# 3_adcs_circuits.net
KiCad netlist of a schematic drawn in Altium Designer
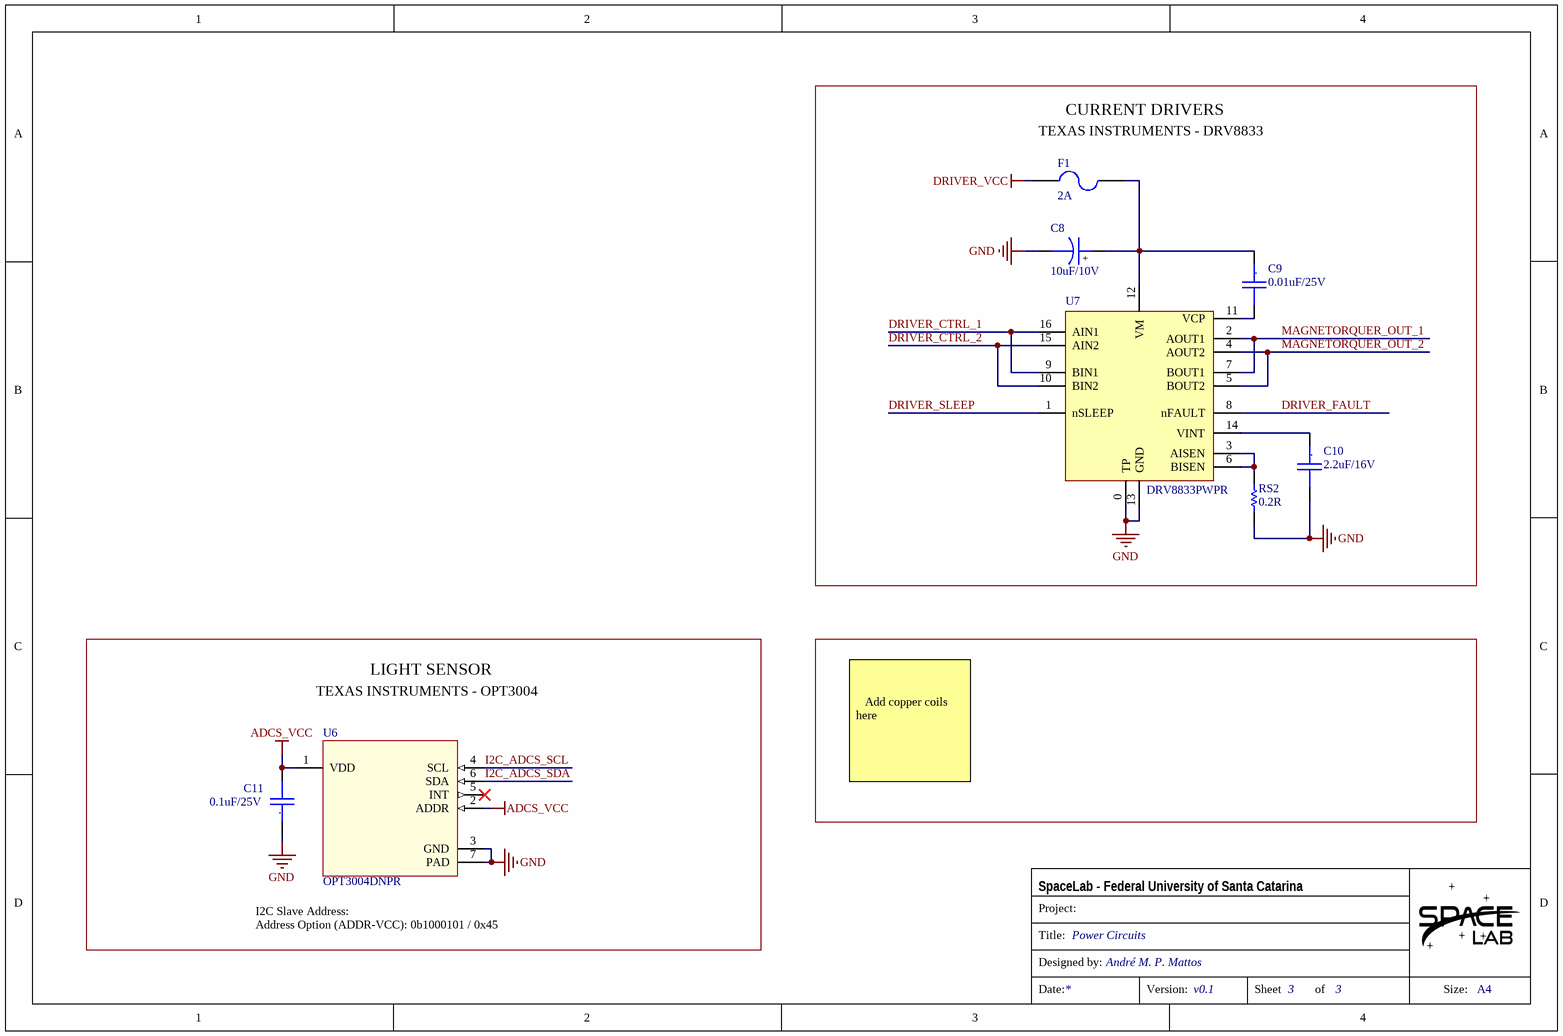
[diagram p0: 3_adcs_circuits.schdoc]

(export (version "E")
  (design (tool "Eeschema 10.0.6"))
  (components
    (comp (ref "C8")
      (value "10uF/10V")
      (footprint "CC0805_Tantalum")
      (description "CAP Tantalum 10uF 10V 20% 0805")
      (fields (field (name "PARTNUMBER") "TPSP106M010R2000"))
      (libsource (lib "schematics_library_legacy") (part "Cap_Tant_SMD_10uF_10V_0805"))
    )
    (comp (ref "C9")
      (value "0.01uF/25V")
      (footprint "CC0805")
      (description "CAP CER 0.01uF 25V 10% X7R 0805")
      (fields (field (name "PARTNUMBER") "CL21B103KAANNNC"))
      (libsource (lib "schematics_library_legacy") (part "Cap_Cer_X7R_0.01uF_50V_0805"))
    )
    (comp (ref "C10")
      (value "2.2uF/16V")
      (footprint "CC0805")
      (description "CAP CER 2.2uF 16V 10% X7R 0805")
      (fields (field (name "PARTNUMBER") "EMF212B7225KGHT"))
      (libsource (lib "schematics_library_legacy") (part "Cap_Cer_X7R_2.2uF_16V_0805"))
    )
    (comp (ref "C11")
      (value "0.1uF/25V")
      (footprint "CC0805")
      (description "CAP CER 0.1UF 25V 10% X7R 0805")
      (fields (field (name "PARTNUMBER") "CC0805KRX7R8BB104"))
      (libsource (lib "schematics_library_legacy") (part "Cap_Cer_X7R_0.1uF_25V_0805"))
    )
    (comp (ref "F1")
      (value "2A")
      (footprint "1206")
      (description "Surface Mount Fuses SMD 1206 Fast Action 2A")
      (fields (field (name "PARTNUMBER") "SF-1206FP200-2"))
      (libsource (lib "schematics_library_legacy") (part "Fuse"))
    )
    (comp (ref "RS2")
      (value "0.2R")
      (footprint "0805")
      (description "RES 0.2R OHM 1/4W 1% 0805")
      (fields (field (name "PARTNUMBER") "ERJ-U6SFR20V"))
      (libsource (lib "schematics_library_legacy") (part "R0.2_1%_1/4W_0805"))
    )
    (comp (ref "U6")
      (value "OPT3004DNPR")
      (footprint "DNP0006A")
      (description "No Description Available")
      (fields
        (field (name "MANUFACTURER") "Texas Instruments")
        (field (name "COPYRIGHT") "Copyright (C) 2018 Accelerated Designs. All rights reserved")
      )
      (libsource (lib "schematics_library_legacy") (part "OPT3004DNPR"))
    )
    (comp (ref "U7")
      (value "DRV8833PWPR")
      (footprint "16TTSSOP")
      (libsource (lib "schematics_library_legacy") (part "DRV8833PWPR"))
    )
  )
  (nets
    (net (code "1") (name "/DRIVER_CTRL_1") (class "Default")
      (node (ref "U7") (pin "16") (pinfunction "AIN1_16") (pintype "passive"))
      (node (ref "U7") (pin "9") (pinfunction "BIN1_9") (pintype "passive"))
    )
    (net (code "2") (name "/DRIVER_CTRL_2") (class "Default")
      (node (ref "U7") (pin "10") (pinfunction "BIN2_10") (pintype "passive"))
      (node (ref "U7") (pin "15") (pinfunction "AIN2_15") (pintype "passive"))
    )
    (net (code "3") (name "/DRIVER_FAULT") (class "Default")
      (node (ref "U7") (pin "8") (pinfunction "nFAULT_8") (pintype "passive"))
    )
    (net (code "4") (name "/DRIVER_SLEEP") (class "Default")
      (node (ref "U7") (pin "1") (pinfunction "nSLEEP_1") (pintype "passive"))
    )
    (net (code "5") (name "/I2C_ADCS_SCL") (class "Default")
      (node (ref "U6") (pin "4") (pinfunction "SCL_4") (pintype "input"))
    )
    (net (code "6") (name "/I2C_ADCS_SDA") (class "Default")
      (node (ref "U6") (pin "6") (pinfunction "SDA_6") (pintype "input"))
    )
    (net (code "7") (name "/MAGNETORQUER_OUT_1") (class "Default")
      (node (ref "U7") (pin "2") (pinfunction "AOUT1_2") (pintype "passive"))
      (node (ref "U7") (pin "7") (pinfunction "BOUT1_7") (pintype "passive"))
    )
    (net (code "8") (name "/MAGNETORQUER_OUT_2") (class "Default")
      (node (ref "U7") (pin "4") (pinfunction "AOUT2_4") (pintype "passive"))
      (node (ref "U7") (pin "5") (pinfunction "BOUT2_5") (pintype "passive"))
    )
    (net (code "9") (name "ADCS_VCC") (class "Default")
      (node (ref "C11") (pin "2") (pinfunction "2_2") (pintype "passive"))
      (node (ref "U6") (pin "1") (pinfunction "VDD_1") (pintype "power_in"))
      (node (ref "U6") (pin "2") (pinfunction "ADDR_2") (pintype "input"))
    )
    (net (code "10") (name "DRIVER_VCC") (class "Default")
      (node (ref "F1") (pin "2") (pinfunction "2_2") (pintype "passive"))
    )
    (net (code "11") (name "GND") (class "Default")
      (node (ref "C10") (pin "2") (pinfunction "2_2") (pintype "passive"))
      (node (ref "C11") (pin "1") (pinfunction "1_1") (pintype "passive"))
      (node (ref "C8") (pin "2") (pinfunction "2_2") (pintype "passive"))
      (node (ref "RS2") (pin "1") (pinfunction "1_1") (pintype "passive"))
      (node (ref "U6") (pin "3") (pinfunction "GND_3") (pintype "power_in"))
      (node (ref "U6") (pin "7") (pinfunction "PAD_7") (pintype "passive"))
      (node (ref "U7") (pin "0") (pinfunction "TP_0") (pintype "passive"))
      (node (ref "U7") (pin "13") (pinfunction "GND_13") (pintype "passive"))
    )
    (net (code "12") (name "Net-(U7-AISEN)") (class "Default")
      (node (ref "RS2") (pin "2") (pinfunction "2_2") (pintype "passive"))
      (node (ref "U7") (pin "3") (pinfunction "AISEN_3") (pintype "passive"))
      (node (ref "U7") (pin "6") (pinfunction "BISEN_6") (pintype "passive"))
    )
    (net (code "13") (name "Net-(U7-VCP)") (class "Default")
      (node (ref "C9") (pin "2") (pinfunction "2_2") (pintype "passive"))
      (node (ref "U7") (pin "11") (pinfunction "VCP_11") (pintype "passive"))
    )
    (net (code "14") (name "Net-(U7-VINT)") (class "Default")
      (node (ref "C10") (pin "1") (pinfunction "1_1") (pintype "passive"))
      (node (ref "U7") (pin "14") (pinfunction "VINT_14") (pintype "passive"))
    )
    (net (code "15") (name "Net-(U7-VM)") (class "Default")
      (node (ref "C8") (pin "1") (pinfunction "1_1") (pintype "passive"))
      (node (ref "C9") (pin "1") (pinfunction "1_1") (pintype "passive"))
      (node (ref "F1") (pin "1") (pinfunction "1_1") (pintype "passive"))
      (node (ref "U7") (pin "12") (pinfunction "VM_12") (pintype "passive"))
    )
    (net (code "16") (name "unconnected-(U6-INT-Pad5)") (class "Default")
      (node (ref "U6") (pin "5") (pinfunction "INT_5") (pintype "output+no_connect"))
    )
  )
)
